# Beat_Box_Schematic.net
KiCad netlist of a schematic drawn in Altium Designer
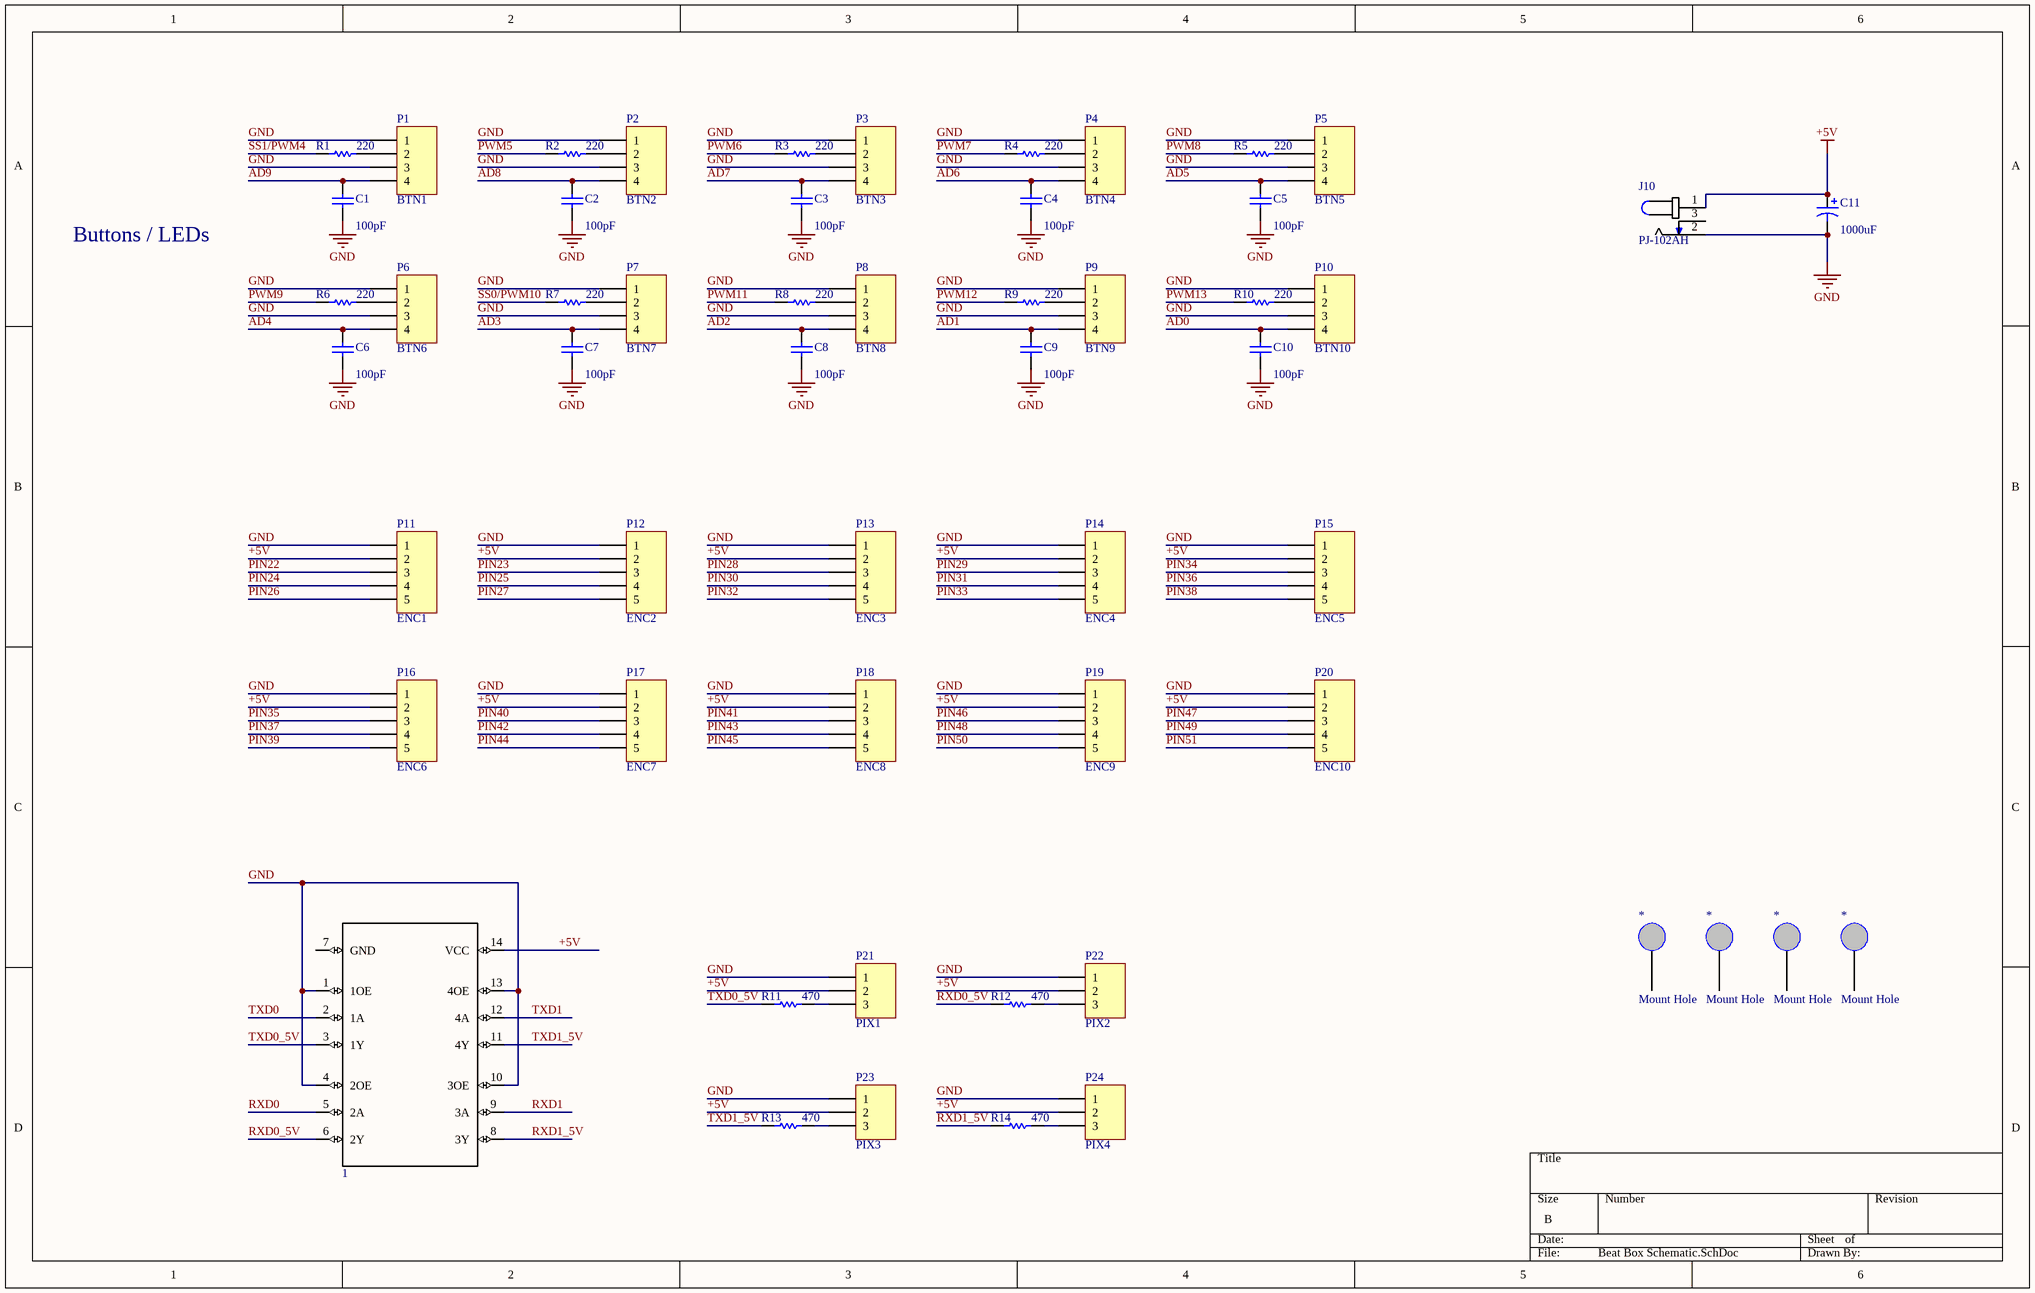
[diagram p0: Beat Box Schematic.SchDoc]

(export (version "E")
  (design (tool "Eeschema 10.0.6"))
  (components
    (comp (ref "*")
      (value "Mount Hole")
      (footprint "6-32 Mount Hole")
      (libsource (lib "schematic library") (part "Mount Hole"))
    )
    (comp (ref "1")
      (value "74AHC125")
      (footprint "*14DIP")
      (fields (field (name "MF") "Texas Instruments"))
      (libsource (lib "74AHC125") (part "74AHC125"))
    )
    (comp (ref "C1")
      (value "100pF")
      (footprint "RAD-0.2")
      (description "Capacitor")
      (fields (field (name "Comment") "Cap") (field (name "PUBLISHER") "Altium Limited"))
      (libsource (lib "Miscellaneous Devices") (part "Cap"))
    )
    (comp (ref "C2")
      (value "100pF")
      (footprint "RAD-0.2")
      (description "Capacitor")
      (fields (field (name "Comment") "Cap") (field (name "PUBLISHER") "Altium Limited"))
      (libsource (lib "Miscellaneous Devices") (part "Cap"))
    )
    (comp (ref "C3")
      (value "100pF")
      (footprint "RAD-0.2")
      (description "Capacitor")
      (fields (field (name "Comment") "Cap") (field (name "PUBLISHER") "Altium Limited"))
      (libsource (lib "Miscellaneous Devices") (part "Cap"))
    )
    (comp (ref "C4")
      (value "100pF")
      (footprint "RAD-0.2")
      (description "Capacitor")
      (fields (field (name "Comment") "Cap") (field (name "PUBLISHER") "Altium Limited"))
      (libsource (lib "Miscellaneous Devices") (part "Cap"))
    )
    (comp (ref "C5")
      (value "100pF")
      (footprint "RAD-0.2")
      (description "Capacitor")
      (fields (field (name "Comment") "Cap") (field (name "PUBLISHER") "Altium Limited"))
      (libsource (lib "Miscellaneous Devices") (part "Cap"))
    )
    (comp (ref "C6")
      (value "100pF")
      (footprint "RAD-0.2")
      (description "Capacitor")
      (fields (field (name "Comment") "Cap") (field (name "PUBLISHER") "Altium Limited"))
      (libsource (lib "Miscellaneous Devices") (part "Cap"))
    )
    (comp (ref "C7")
      (value "100pF")
      (footprint "RAD-0.2")
      (description "Capacitor")
      (fields (field (name "Comment") "Cap") (field (name "PUBLISHER") "Altium Limited"))
      (libsource (lib "Miscellaneous Devices") (part "Cap"))
    )
    (comp (ref "C8")
      (value "100pF")
      (footprint "RAD-0.2")
      (description "Capacitor")
      (fields (field (name "Comment") "Cap") (field (name "PUBLISHER") "Altium Limited"))
      (libsource (lib "Miscellaneous Devices") (part "Cap"))
    )
    (comp (ref "C9")
      (value "100pF")
      (footprint "RAD-0.2")
      (description "Capacitor")
      (fields (field (name "Comment") "Cap") (field (name "PUBLISHER") "Altium Limited"))
      (libsource (lib "Miscellaneous Devices") (part "Cap"))
    )
    (comp (ref "C10")
      (value "100pF")
      (footprint "RAD-0.2")
      (description "Capacitor")
      (fields (field (name "Comment") "Cap") (field (name "PUBLISHER") "Altium Limited"))
      (libsource (lib "Miscellaneous Devices") (part "Cap"))
    )
    (comp (ref "C11")
      (value "1000uF")
      (footprint "RB7.6-15")
      (description "Polarized Capacitor (Radial)")
      (fields (field (name "Comment") "Cap Pol1") (field (name "PUBLISHER") "Altium Limited"))
      (libsource (lib "Miscellaneous Devices") (part "Cap Pol1"))
    )
    (comp (ref "J10")
      (value "PJ-102AH")
      (footprint "*CUI_PJ-102AH")
      (libsource (lib "PJ-102AH") (part "PJ-102AH"))
    )
    (comp (ref "P1")
      (value "BTN1")
      (footprint "HDR1X4")
      (description "Header, 4-Pin")
      (fields (field (name "PUBLISHER") "Altium Limited"))
      (libsource (lib "Miscellaneous Connectors") (part "Header 4"))
    )
    (comp (ref "P2")
      (value "BTN2")
      (footprint "HDR1X4")
      (description "Header, 4-Pin")
      (fields (field (name "PUBLISHER") "Altium Limited"))
      (libsource (lib "Miscellaneous Connectors") (part "Header 4"))
    )
    (comp (ref "P3")
      (value "BTN3")
      (footprint "HDR1X4")
      (description "Header, 4-Pin")
      (fields (field (name "PUBLISHER") "Altium Limited"))
      (libsource (lib "Miscellaneous Connectors") (part "Header 4"))
    )
    (comp (ref "P4")
      (value "BTN4")
      (footprint "HDR1X4")
      (description "Header, 4-Pin")
      (fields (field (name "PUBLISHER") "Altium Limited"))
      (libsource (lib "Miscellaneous Connectors") (part "Header 4"))
    )
    (comp (ref "P5")
      (value "BTN5")
      (footprint "HDR1X4")
      (description "Header, 4-Pin")
      (fields (field (name "PUBLISHER") "Altium Limited"))
      (libsource (lib "Miscellaneous Connectors") (part "Header 4"))
    )
    (comp (ref "P6")
      (value "BTN6")
      (footprint "HDR1X4")
      (description "Header, 4-Pin")
      (fields (field (name "PUBLISHER") "Altium Limited"))
      (libsource (lib "Miscellaneous Connectors") (part "Header 4"))
    )
    (comp (ref "P7")
      (value "BTN7")
      (footprint "HDR1X4")
      (description "Header, 4-Pin")
      (fields (field (name "PUBLISHER") "Altium Limited"))
      (libsource (lib "Miscellaneous Connectors") (part "Header 4"))
    )
    (comp (ref "P8")
      (value "BTN8")
      (footprint "HDR1X4")
      (description "Header, 4-Pin")
      (fields (field (name "PUBLISHER") "Altium Limited"))
      (libsource (lib "Miscellaneous Connectors") (part "Header 4"))
    )
    (comp (ref "P9")
      (value "BTN9")
      (footprint "HDR1X4")
      (description "Header, 4-Pin")
      (fields (field (name "PUBLISHER") "Altium Limited"))
      (libsource (lib "Miscellaneous Connectors") (part "Header 4"))
    )
    (comp (ref "P10")
      (value "BTN10")
      (footprint "HDR1X4")
      (description "Header, 4-Pin")
      (fields (field (name "PUBLISHER") "Altium Limited"))
      (libsource (lib "Miscellaneous Connectors") (part "Header 4"))
    )
    (comp (ref "P11")
      (value "ENC1")
      (footprint "HDR1X5")
      (description "Header, 5-Pin")
      (fields (field (name "PUBLISHER") "Altium Limited"))
      (libsource (lib "Miscellaneous Connectors") (part "Header 5"))
    )
    (comp (ref "P12")
      (value "ENC2")
      (footprint "HDR1X5")
      (description "Header, 5-Pin")
      (fields (field (name "PUBLISHER") "Altium Limited"))
      (libsource (lib "Miscellaneous Connectors") (part "Header 5"))
    )
    (comp (ref "P13")
      (value "ENC3")
      (footprint "HDR1X5")
      (description "Header, 5-Pin")
      (fields (field (name "PUBLISHER") "Altium Limited"))
      (libsource (lib "Miscellaneous Connectors") (part "Header 5"))
    )
    (comp (ref "P14")
      (value "ENC4")
      (footprint "HDR1X5")
      (description "Header, 5-Pin")
      (fields (field (name "PUBLISHER") "Altium Limited"))
      (libsource (lib "Miscellaneous Connectors") (part "Header 5"))
    )
    (comp (ref "P15")
      (value "ENC5")
      (footprint "HDR1X5")
      (description "Header, 5-Pin")
      (fields (field (name "PUBLISHER") "Altium Limited"))
      (libsource (lib "Miscellaneous Connectors") (part "Header 5"))
    )
    (comp (ref "P16")
      (value "ENC6")
      (footprint "HDR1X5")
      (description "Header, 5-Pin")
      (fields (field (name "PUBLISHER") "Altium Limited"))
      (libsource (lib "Miscellaneous Connectors") (part "Header 5"))
    )
    (comp (ref "P17")
      (value "ENC7")
      (footprint "HDR1X5")
      (description "Header, 5-Pin")
      (fields (field (name "PUBLISHER") "Altium Limited"))
      (libsource (lib "Miscellaneous Connectors") (part "Header 5"))
    )
    (comp (ref "P18")
      (value "ENC8")
      (footprint "HDR1X5")
      (description "Header, 5-Pin")
      (fields (field (name "PUBLISHER") "Altium Limited"))
      (libsource (lib "Miscellaneous Connectors") (part "Header 5"))
    )
    (comp (ref "P19")
      (value "ENC9")
      (footprint "HDR1X5")
      (description "Header, 5-Pin")
      (fields (field (name "PUBLISHER") "Altium Limited"))
      (libsource (lib "Miscellaneous Connectors") (part "Header 5"))
    )
    (comp (ref "P20")
      (value "ENC10")
      (footprint "HDR1X5")
      (description "Header, 5-Pin")
      (fields (field (name "PUBLISHER") "Altium Limited"))
      (libsource (lib "Miscellaneous Connectors") (part "Header 5"))
    )
    (comp (ref "P21")
      (value "PIX1")
      (footprint "HDR1X3")
      (description "Header, 3-Pin")
      (fields (field (name "PUBLISHER") "Altium Limited"))
      (libsource (lib "Miscellaneous Connectors") (part "Header 3"))
    )
    (comp (ref "P22")
      (value "PIX2")
      (footprint "HDR1X3")
      (description "Header, 3-Pin")
      (fields (field (name "PUBLISHER") "Altium Limited"))
      (libsource (lib "Miscellaneous Connectors") (part "Header 3"))
    )
    (comp (ref "P23")
      (value "PIX3")
      (footprint "HDR1X3")
      (description "Header, 3-Pin")
      (fields (field (name "PUBLISHER") "Altium Limited"))
      (libsource (lib "Miscellaneous Connectors") (part "Header 3"))
    )
    (comp (ref "P24")
      (value "PIX4")
      (footprint "HDR1X3")
      (description "Header, 3-Pin")
      (fields (field (name "PUBLISHER") "Altium Limited"))
      (libsource (lib "Miscellaneous Connectors") (part "Header 3"))
    )
    (comp (ref "R1")
      (value "220")
      (footprint "AXIAL-0.3")
      (description "Resistor")
      (fields (field (name "Comment") "Res1") (field (name "PUBLISHER") "Altium Limited"))
      (libsource (lib "Miscellaneous Devices") (part "Res1"))
    )
    (comp (ref "R2")
      (value "220")
      (footprint "AXIAL-0.3")
      (description "Resistor")
      (fields (field (name "Comment") "Res1") (field (name "PUBLISHER") "Altium Limited"))
      (libsource (lib "Miscellaneous Devices") (part "Res1"))
    )
    (comp (ref "R3")
      (value "220")
      (footprint "AXIAL-0.3")
      (description "Resistor")
      (fields (field (name "Comment") "Res1") (field (name "PUBLISHER") "Altium Limited"))
      (libsource (lib "Miscellaneous Devices") (part "Res1"))
    )
    (comp (ref "R4")
      (value "220")
      (footprint "AXIAL-0.3")
      (description "Resistor")
      (fields (field (name "Comment") "Res1") (field (name "PUBLISHER") "Altium Limited"))
      (libsource (lib "Miscellaneous Devices") (part "Res1"))
    )
    (comp (ref "R5")
      (value "220")
      (footprint "AXIAL-0.3")
      (description "Resistor")
      (fields (field (name "Comment") "Res1") (field (name "PUBLISHER") "Altium Limited"))
      (libsource (lib "Miscellaneous Devices") (part "Res1"))
    )
    (comp (ref "R6")
      (value "220")
      (footprint "AXIAL-0.3")
      (description "Resistor")
      (fields (field (name "Comment") "Res1") (field (name "PUBLISHER") "Altium Limited"))
      (libsource (lib "Miscellaneous Devices") (part "Res1"))
    )
    (comp (ref "R7")
      (value "220")
      (footprint "AXIAL-0.3")
      (description "Resistor")
      (fields (field (name "Comment") "Res1") (field (name "PUBLISHER") "Altium Limited"))
      (libsource (lib "Miscellaneous Devices") (part "Res1"))
    )
    (comp (ref "R8")
      (value "220")
      (footprint "AXIAL-0.3")
      (description "Resistor")
      (fields (field (name "Comment") "Res1") (field (name "PUBLISHER") "Altium Limited"))
      (libsource (lib "Miscellaneous Devices") (part "Res1"))
    )
    (comp (ref "R9")
      (value "220")
      (footprint "AXIAL-0.3")
      (description "Resistor")
      (fields (field (name "Comment") "Res1") (field (name "PUBLISHER") "Altium Limited"))
      (libsource (lib "Miscellaneous Devices") (part "Res1"))
    )
    (comp (ref "R10")
      (value "220")
      (footprint "AXIAL-0.3")
      (description "Resistor")
      (fields (field (name "Comment") "Res1") (field (name "PUBLISHER") "Altium Limited"))
      (libsource (lib "Miscellaneous Devices") (part "Res1"))
    )
    (comp (ref "R11")
      (value "470")
      (footprint "AXIAL-0.3")
      (description "Resistor")
      (fields (field (name "Comment") "Res1") (field (name "PUBLISHER") "Altium Limited"))
      (libsource (lib "Miscellaneous Devices") (part "Res1"))
    )
    (comp (ref "R12")
      (value "470")
      (footprint "AXIAL-0.3")
      (description "Resistor")
      (fields (field (name "Comment") "Res1") (field (name "PUBLISHER") "Altium Limited"))
      (libsource (lib "Miscellaneous Devices") (part "Res1"))
    )
    (comp (ref "R13")
      (value "470")
      (footprint "AXIAL-0.3")
      (description "Resistor")
      (fields (field (name "Comment") "Res1") (field (name "PUBLISHER") "Altium Limited"))
      (libsource (lib "Miscellaneous Devices") (part "Res1"))
    )
    (comp (ref "R14")
      (value "470")
      (footprint "AXIAL-0.3")
      (description "Resistor")
      (fields (field (name "Comment") "Res1") (field (name "PUBLISHER") "Altium Limited"))
      (libsource (lib "Miscellaneous Devices") (part "Res1"))
    )
  )
  (nets
    (net (code "1") (name "+5V") (class "Default")
      (node (ref "1") (pin "14") (pinfunction "VCC_14") (pintype "bidirectional"))
      (node (ref "C11") (pin "1") (pinfunction "1_1") (pintype "passive"))
      (node (ref "J10") (pin "1") (pinfunction "1_1") (pintype "passive"))
      (node (ref "P11") (pin "2") (pinfunction "2_2") (pintype "passive"))
      (node (ref "P12") (pin "2") (pinfunction "2_2") (pintype "passive"))
      (node (ref "P13") (pin "2") (pinfunction "2_2") (pintype "passive"))
      (node (ref "P14") (pin "2") (pinfunction "2_2") (pintype "passive"))
      (node (ref "P15") (pin "2") (pinfunction "2_2") (pintype "passive"))
      (node (ref "P16") (pin "2") (pinfunction "2_2") (pintype "passive"))
      (node (ref "P17") (pin "2") (pinfunction "2_2") (pintype "passive"))
      (node (ref "P18") (pin "2") (pinfunction "2_2") (pintype "passive"))
      (node (ref "P19") (pin "2") (pinfunction "2_2") (pintype "passive"))
      (node (ref "P20") (pin "2") (pinfunction "2_2") (pintype "passive"))
      (node (ref "P21") (pin "2") (pinfunction "2_2") (pintype "passive"))
      (node (ref "P22") (pin "2") (pinfunction "2_2") (pintype "passive"))
      (node (ref "P23") (pin "2") (pinfunction "2_2") (pintype "passive"))
      (node (ref "P24") (pin "2") (pinfunction "2_2") (pintype "passive"))
    )
    (net (code "2") (name "/AD0") (class "Default")
      (node (ref "C10") (pin "2") (pinfunction "2_2") (pintype "passive"))
      (node (ref "P10") (pin "4") (pinfunction "4_4") (pintype "passive"))
    )
    (net (code "3") (name "/AD1") (class "Default")
      (node (ref "C9") (pin "2") (pinfunction "2_2") (pintype "passive"))
      (node (ref "P9") (pin "4") (pinfunction "4_4") (pintype "passive"))
    )
    (net (code "4") (name "/AD2") (class "Default")
      (node (ref "C8") (pin "2") (pinfunction "2_2") (pintype "passive"))
      (node (ref "P8") (pin "4") (pinfunction "4_4") (pintype "passive"))
    )
    (net (code "5") (name "/AD3") (class "Default")
      (node (ref "C7") (pin "2") (pinfunction "2_2") (pintype "passive"))
      (node (ref "P7") (pin "4") (pinfunction "4_4") (pintype "passive"))
    )
    (net (code "6") (name "/AD4") (class "Default")
      (node (ref "C6") (pin "2") (pinfunction "2_2") (pintype "passive"))
      (node (ref "P6") (pin "4") (pinfunction "4_4") (pintype "passive"))
    )
    (net (code "7") (name "/AD5") (class "Default")
      (node (ref "C5") (pin "2") (pinfunction "2_2") (pintype "passive"))
      (node (ref "P5") (pin "4") (pinfunction "4_4") (pintype "passive"))
    )
    (net (code "8") (name "/AD6") (class "Default")
      (node (ref "C4") (pin "2") (pinfunction "2_2") (pintype "passive"))
      (node (ref "P4") (pin "4") (pinfunction "4_4") (pintype "passive"))
    )
    (net (code "9") (name "/AD7") (class "Default")
      (node (ref "C3") (pin "2") (pinfunction "2_2") (pintype "passive"))
      (node (ref "P3") (pin "4") (pinfunction "4_4") (pintype "passive"))
    )
    (net (code "10") (name "/AD8") (class "Default")
      (node (ref "C2") (pin "2") (pinfunction "2_2") (pintype "passive"))
      (node (ref "P2") (pin "4") (pinfunction "4_4") (pintype "passive"))
    )
    (net (code "11") (name "/AD9") (class "Default")
      (node (ref "C1") (pin "2") (pinfunction "2_2") (pintype "passive"))
      (node (ref "P1") (pin "4") (pinfunction "4_4") (pintype "passive"))
    )
    (net (code "12") (name "/PIN22") (class "Default")
      (node (ref "P11") (pin "3") (pinfunction "3_3") (pintype "passive"))
    )
    (net (code "13") (name "/PIN23") (class "Default")
      (node (ref "P12") (pin "3") (pinfunction "3_3") (pintype "passive"))
    )
    (net (code "14") (name "/PIN24") (class "Default")
      (node (ref "P11") (pin "4") (pinfunction "4_4") (pintype "passive"))
    )
    (net (code "15") (name "/PIN25") (class "Default")
      (node (ref "P12") (pin "4") (pinfunction "4_4") (pintype "passive"))
    )
    (net (code "16") (name "/PIN26") (class "Default")
      (node (ref "P11") (pin "5") (pinfunction "5_5") (pintype "passive"))
    )
    (net (code "17") (name "/PIN27") (class "Default")
      (node (ref "P12") (pin "5") (pinfunction "5_5") (pintype "passive"))
    )
    (net (code "18") (name "/PIN28") (class "Default")
      (node (ref "P13") (pin "3") (pinfunction "3_3") (pintype "passive"))
    )
    (net (code "19") (name "/PIN29") (class "Default")
      (node (ref "P14") (pin "3") (pinfunction "3_3") (pintype "passive"))
    )
    (net (code "20") (name "/PIN30") (class "Default")
      (node (ref "P13") (pin "4") (pinfunction "4_4") (pintype "passive"))
    )
    (net (code "21") (name "/PIN31") (class "Default")
      (node (ref "P14") (pin "4") (pinfunction "4_4") (pintype "passive"))
    )
    (net (code "22") (name "/PIN32") (class "Default")
      (node (ref "P13") (pin "5") (pinfunction "5_5") (pintype "passive"))
    )
    (net (code "23") (name "/PIN33") (class "Default")
      (node (ref "P14") (pin "5") (pinfunction "5_5") (pintype "passive"))
    )
    (net (code "24") (name "/PIN34") (class "Default")
      (node (ref "P15") (pin "3") (pinfunction "3_3") (pintype "passive"))
    )
    (net (code "25") (name "/PIN35") (class "Default")
      (node (ref "P16") (pin "3") (pinfunction "3_3") (pintype "passive"))
    )
    (net (code "26") (name "/PIN36") (class "Default")
      (node (ref "P15") (pin "4") (pinfunction "4_4") (pintype "passive"))
    )
    (net (code "27") (name "/PIN37") (class "Default")
      (node (ref "P16") (pin "4") (pinfunction "4_4") (pintype "passive"))
    )
    (net (code "28") (name "/PIN38") (class "Default")
      (node (ref "P15") (pin "5") (pinfunction "5_5") (pintype "passive"))
    )
    (net (code "29") (name "/PIN39") (class "Default")
      (node (ref "P16") (pin "5") (pinfunction "5_5") (pintype "passive"))
    )
    (net (code "30") (name "/PIN40") (class "Default")
      (node (ref "P17") (pin "3") (pinfunction "3_3") (pintype "passive"))
    )
    (net (code "31") (name "/PIN41") (class "Default")
      (node (ref "P18") (pin "3") (pinfunction "3_3") (pintype "passive"))
    )
    (net (code "32") (name "/PIN42") (class "Default")
      (node (ref "P17") (pin "4") (pinfunction "4_4") (pintype "passive"))
    )
    (net (code "33") (name "/PIN43") (class "Default")
      (node (ref "P18") (pin "4") (pinfunction "4_4") (pintype "passive"))
    )
    (net (code "34") (name "/PIN44") (class "Default")
      (node (ref "P17") (pin "5") (pinfunction "5_5") (pintype "passive"))
    )
    (net (code "35") (name "/PIN45") (class "Default")
      (node (ref "P18") (pin "5") (pinfunction "5_5") (pintype "passive"))
    )
    (net (code "36") (name "/PIN46") (class "Default")
      (node (ref "P19") (pin "3") (pinfunction "3_3") (pintype "passive"))
    )
    (net (code "37") (name "/PIN47") (class "Default")
      (node (ref "P20") (pin "3") (pinfunction "3_3") (pintype "passive"))
    )
    (net (code "38") (name "/PIN48") (class "Default")
      (node (ref "P19") (pin "4") (pinfunction "4_4") (pintype "passive"))
    )
    (net (code "39") (name "/PIN49") (class "Default")
      (node (ref "P20") (pin "4") (pinfunction "4_4") (pintype "passive"))
    )
    (net (code "40") (name "/PIN50") (class "Default")
      (node (ref "P19") (pin "5") (pinfunction "5_5") (pintype "passive"))
    )
    (net (code "41") (name "/PIN51") (class "Default")
      (node (ref "P20") (pin "5") (pinfunction "5_5") (pintype "passive"))
    )
    (net (code "42") (name "/PWM5") (class "Default")
      (node (ref "R2") (pin "1") (pinfunction "1_1") (pintype "passive"))
    )
    (net (code "43") (name "/PWM6") (class "Default")
      (node (ref "R3") (pin "1") (pinfunction "1_1") (pintype "passive"))
    )
    (net (code "44") (name "/PWM7") (class "Default")
      (node (ref "R4") (pin "1") (pinfunction "1_1") (pintype "passive"))
    )
    (net (code "45") (name "/PWM8") (class "Default")
      (node (ref "R5") (pin "1") (pinfunction "1_1") (pintype "passive"))
    )
    (net (code "46") (name "/PWM9") (class "Default")
      (node (ref "R6") (pin "1") (pinfunction "1_1") (pintype "passive"))
    )
    (net (code "47") (name "/PWM11") (class "Default")
      (node (ref "R8") (pin "1") (pinfunction "1_1") (pintype "passive"))
    )
    (net (code "48") (name "/PWM12") (class "Default")
      (node (ref "R9") (pin "1") (pinfunction "1_1") (pintype "passive"))
    )
    (net (code "49") (name "/PWM13") (class "Default")
      (node (ref "R10") (pin "1") (pinfunction "1_1") (pintype "passive"))
    )
    (net (code "50") (name "/RXD0") (class "Default")
      (node (ref "1") (pin "5") (pinfunction "2A_5") (pintype "bidirectional"))
    )
    (net (code "51") (name "/RXD0_5V") (class "Default")
      (node (ref "1") (pin "6") (pinfunction "2Y_6") (pintype "bidirectional"))
      (node (ref "R12") (pin "1") (pinfunction "1_1") (pintype "passive"))
    )
    (net (code "52") (name "/RXD1") (class "Default")
      (node (ref "1") (pin "9") (pinfunction "3A_9") (pintype "bidirectional"))
    )
    (net (code "53") (name "/RXD1_5V") (class "Default")
      (node (ref "1") (pin "8") (pinfunction "3Y_8") (pintype "bidirectional"))
      (node (ref "R14") (pin "1") (pinfunction "1_1") (pintype "passive"))
    )
    (net (code "54") (name "/SS0{slash}PWM10") (class "Default")
      (node (ref "R7") (pin "1") (pinfunction "1_1") (pintype "passive"))
    )
    (net (code "55") (name "/SS1{slash}PWM4") (class "Default")
      (node (ref "R1") (pin "1") (pinfunction "1_1") (pintype "passive"))
    )
    (net (code "56") (name "/TXD0") (class "Default")
      (node (ref "1") (pin "2") (pinfunction "1A_2") (pintype "bidirectional"))
    )
    (net (code "57") (name "/TXD0_5V") (class "Default")
      (node (ref "1") (pin "3") (pinfunction "1Y_3") (pintype "bidirectional"))
      (node (ref "R11") (pin "1") (pinfunction "1_1") (pintype "passive"))
    )
    (net (code "58") (name "/TXD1") (class "Default")
      (node (ref "1") (pin "12") (pinfunction "4A_12") (pintype "bidirectional"))
    )
    (net (code "59") (name "/TXD1_5V") (class "Default")
      (node (ref "1") (pin "11") (pinfunction "4Y_11") (pintype "bidirectional"))
      (node (ref "R13") (pin "1") (pinfunction "1_1") (pintype "passive"))
    )
    (net (code "60") (name "GND") (class "Default")
      (node (ref "1") (pin "1") (pinfunction "1OE_1") (pintype "bidirectional"))
      (node (ref "1") (pin "10") (pinfunction "3OE_10") (pintype "bidirectional"))
      (node (ref "1") (pin "13") (pinfunction "4OE_13") (pintype "bidirectional"))
      (node (ref "1") (pin "4") (pinfunction "2OE_4") (pintype "bidirectional"))
      (node (ref "C1") (pin "1") (pinfunction "1_1") (pintype "passive"))
      (node (ref "C10") (pin "1") (pinfunction "1_1") (pintype "passive"))
      (node (ref "C11") (pin "2") (pinfunction "2_2") (pintype "passive"))
      (node (ref "C2") (pin "1") (pinfunction "1_1") (pintype "passive"))
      (node (ref "C3") (pin "1") (pinfunction "1_1") (pintype "passive"))
      (node (ref "C4") (pin "1") (pinfunction "1_1") (pintype "passive"))
      (node (ref "C5") (pin "1") (pinfunction "1_1") (pintype "passive"))
      (node (ref "C6") (pin "1") (pinfunction "1_1") (pintype "passive"))
      (node (ref "C7") (pin "1") (pinfunction "1_1") (pintype "passive"))
      (node (ref "C8") (pin "1") (pinfunction "1_1") (pintype "passive"))
      (node (ref "C9") (pin "1") (pinfunction "1_1") (pintype "passive"))
      (node (ref "J10") (pin "2") (pinfunction "2_2") (pintype "passive"))
      (node (ref "P1") (pin "1") (pinfunction "1_1") (pintype "passive"))
      (node (ref "P1") (pin "3") (pinfunction "3_3") (pintype "passive"))
      (node (ref "P10") (pin "1") (pinfunction "1_1") (pintype "passive"))
      (node (ref "P10") (pin "3") (pinfunction "3_3") (pintype "passive"))
      (node (ref "P11") (pin "1") (pinfunction "1_1") (pintype "passive"))
      (node (ref "P12") (pin "1") (pinfunction "1_1") (pintype "passive"))
      (node (ref "P13") (pin "1") (pinfunction "1_1") (pintype "passive"))
      (node (ref "P14") (pin "1") (pinfunction "1_1") (pintype "passive"))
      (node (ref "P15") (pin "1") (pinfunction "1_1") (pintype "passive"))
      (node (ref "P16") (pin "1") (pinfunction "1_1") (pintype "passive"))
      (node (ref "P17") (pin "1") (pinfunction "1_1") (pintype "passive"))
      (node (ref "P18") (pin "1") (pinfunction "1_1") (pintype "passive"))
      (node (ref "P19") (pin "1") (pinfunction "1_1") (pintype "passive"))
      (node (ref "P2") (pin "1") (pinfunction "1_1") (pintype "passive"))
      (node (ref "P2") (pin "3") (pinfunction "3_3") (pintype "passive"))
      (node (ref "P20") (pin "1") (pinfunction "1_1") (pintype "passive"))
      (node (ref "P21") (pin "1") (pinfunction "1_1") (pintype "passive"))
      (node (ref "P22") (pin "1") (pinfunction "1_1") (pintype "passive"))
      (node (ref "P23") (pin "1") (pinfunction "1_1") (pintype "passive"))
      (node (ref "P24") (pin "1") (pinfunction "1_1") (pintype "passive"))
      (node (ref "P3") (pin "1") (pinfunction "1_1") (pintype "passive"))
      (node (ref "P3") (pin "3") (pinfunction "3_3") (pintype "passive"))
      (node (ref "P4") (pin "1") (pinfunction "1_1") (pintype "passive"))
      (node (ref "P4") (pin "3") (pinfunction "3_3") (pintype "passive"))
      (node (ref "P5") (pin "1") (pinfunction "1_1") (pintype "passive"))
      (node (ref "P5") (pin "3") (pinfunction "3_3") (pintype "passive"))
      (node (ref "P6") (pin "1") (pinfunction "1_1") (pintype "passive"))
      (node (ref "P6") (pin "3") (pinfunction "3_3") (pintype "passive"))
      (node (ref "P7") (pin "1") (pinfunction "1_1") (pintype "passive"))
      (node (ref "P7") (pin "3") (pinfunction "3_3") (pintype "passive"))
      (node (ref "P8") (pin "1") (pinfunction "1_1") (pintype "passive"))
      (node (ref "P8") (pin "3") (pinfunction "3_3") (pintype "passive"))
      (node (ref "P9") (pin "1") (pinfunction "1_1") (pintype "passive"))
      (node (ref "P9") (pin "3") (pinfunction "3_3") (pintype "passive"))
    )
    (net (code "61") (name "Net-(P1-Pad2)") (class "Default")
      (node (ref "P1") (pin "2") (pinfunction "2_2") (pintype "passive"))
      (node (ref "R1") (pin "2") (pinfunction "2_2") (pintype "passive"))
    )
    (net (code "62") (name "Net-(P2-Pad2)") (class "Default")
      (node (ref "P2") (pin "2") (pinfunction "2_2") (pintype "passive"))
      (node (ref "R2") (pin "2") (pinfunction "2_2") (pintype "passive"))
    )
    (net (code "63") (name "Net-(P3-Pad2)") (class "Default")
      (node (ref "P3") (pin "2") (pinfunction "2_2") (pintype "passive"))
      (node (ref "R3") (pin "2") (pinfunction "2_2") (pintype "passive"))
    )
    (net (code "64") (name "Net-(P4-Pad2)") (class "Default")
      (node (ref "P4") (pin "2") (pinfunction "2_2") (pintype "passive"))
      (node (ref "R4") (pin "2") (pinfunction "2_2") (pintype "passive"))
    )
    (net (code "65") (name "Net-(P5-Pad2)") (class "Default")
      (node (ref "P5") (pin "2") (pinfunction "2_2") (pintype "passive"))
      (node (ref "R5") (pin "2") (pinfunction "2_2") (pintype "passive"))
    )
    (net (code "66") (name "Net-(P6-Pad2)") (class "Default")
      (node (ref "P6") (pin "2") (pinfunction "2_2") (pintype "passive"))
      (node (ref "R6") (pin "2") (pinfunction "2_2") (pintype "passive"))
    )
    (net (code "67") (name "Net-(P7-Pad2)") (class "Default")
      (node (ref "P7") (pin "2") (pinfunction "2_2") (pintype "passive"))
      (node (ref "R7") (pin "2") (pinfunction "2_2") (pintype "passive"))
    )
    (net (code "68") (name "Net-(P8-Pad2)") (class "Default")
      (node (ref "P8") (pin "2") (pinfunction "2_2") (pintype "passive"))
      (node (ref "R8") (pin "2") (pinfunction "2_2") (pintype "passive"))
    )
    (net (code "69") (name "Net-(P9-Pad2)") (class "Default")
      (node (ref "P9") (pin "2") (pinfunction "2_2") (pintype "passive"))
      (node (ref "R9") (pin "2") (pinfunction "2_2") (pintype "passive"))
    )
    (net (code "70") (name "Net-(P10-Pad2)") (class "Default")
      (node (ref "P10") (pin "2") (pinfunction "2_2") (pintype "passive"))
      (node (ref "R10") (pin "2") (pinfunction "2_2") (pintype "passive"))
    )
    (net (code "71") (name "Net-(P21-Pad3)") (class "Default")
      (node (ref "P21") (pin "3") (pinfunction "3_3") (pintype "passive"))
      (node (ref "R11") (pin "2") (pinfunction "2_2") (pintype "passive"))
    )
    (net (code "72") (name "Net-(P22-Pad3)") (class "Default")
      (node (ref "P22") (pin "3") (pinfunction "3_3") (pintype "passive"))
      (node (ref "R12") (pin "2") (pinfunction "2_2") (pintype "passive"))
    )
    (net (code "73") (name "Net-(P23-Pad3)") (class "Default")
      (node (ref "P23") (pin "3") (pinfunction "3_3") (pintype "passive"))
      (node (ref "R13") (pin "2") (pinfunction "2_2") (pintype "passive"))
    )
    (net (code "74") (name "Net-(P24-Pad3)") (class "Default")
      (node (ref "P24") (pin "3") (pinfunction "3_3") (pintype "passive"))
      (node (ref "R14") (pin "2") (pinfunction "2_2") (pintype "passive"))
    )
    (net (code "75") (name "unconnected-(*-Pad0)") (class "Default")
      (node (ref "*") (pin "0") (pinfunction "0_0") (pintype "passive"))
    )
    (net (code "76") (name "unconnected-(*-Pad0)_1") (class "Default")
      (node (ref "*") (pin "0") (pinfunction "0_0") (pintype "passive"))
    )
    (net (code "77") (name "unconnected-(*-Pad0)_2") (class "Default")
      (node (ref "*") (pin "0") (pinfunction "0_0") (pintype "passive"))
    )
    (net (code "78") (name "unconnected-(*-Pad0)_3") (class "Default")
      (node (ref "*") (pin "0") (pinfunction "0_0") (pintype "passive"))
    )
    (net (code "79") (name "unconnected-(1-GND-Pad7)") (class "Default")
      (node (ref "1") (pin "7") (pinfunction "GND_7") (pintype "bidirectional"))
    )
    (net (code "80") (name "unconnected-(J10-Pad3)") (class "Default")
      (node (ref "J10") (pin "3") (pinfunction "3_3") (pintype "passive"))
    )
  )
)
